# Power.net
KiCad netlist of a schematic drawn in Altium Designer
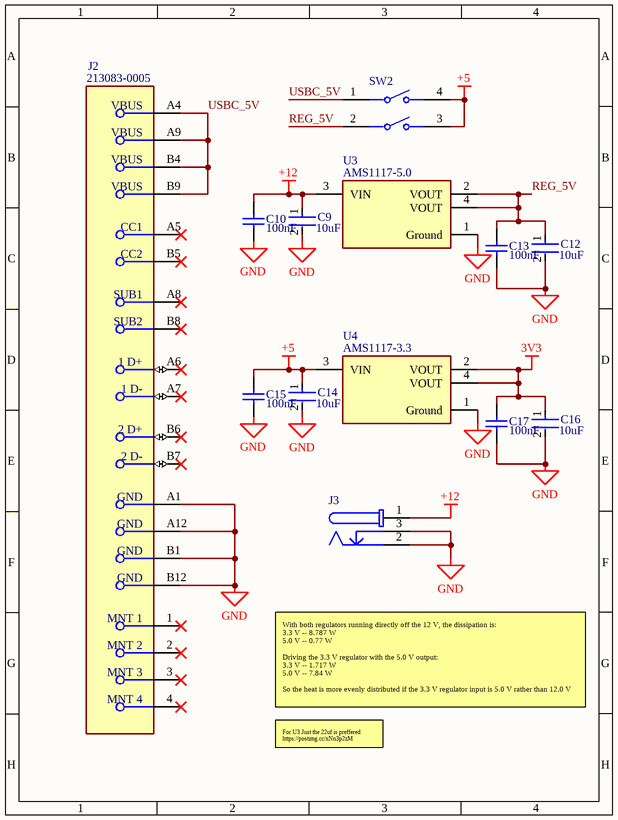
[diagram p0: Power.SchDoc]

(export (version "E")
  (design (tool "Eeschema 10.0.6"))
  (components
    (comp (ref "C9")
      (value "1206YD106KAT2A")
      (footprint "FP-1206-L_3_2_0_2-W_1_6_0-IPC_B")
      (description "General Purpose Ceramic Capacitor, 1206, 10uF, 10%, X5R, 15%, 16V")
      (fields
        (field (name "TOLERANCE") "10%")
        (field (name "CAPACITANCE") "10uF")
        (field (name "VOLTAGE") "16V")
      )
      (libsource (lib "Altium Content Vault") (part "02cd4be3c70576c341d710602a673aa"))
    )
    (comp (ref "C10")
      (value "100nF")
      (footprint "CAPC2013X140X50LL20T25")
      (fields
        (field (name "MANUFACTURER") "AVX Interconnect / Elco")
        (field (name "PART NUMBER") "08055F104KAT2A")
      )
      (libsource (lib "Altium Content Vault") (part "CAP"))
    )
    (comp (ref "C12")
      (value "1206YD106KAT2A")
      (footprint "FP-1206-L_3_2_0_2-W_1_6_0-IPC_B")
      (description "General Purpose Ceramic Capacitor, 1206, 10uF, 10%, X5R, 15%, 16V")
      (fields
        (field (name "TOLERANCE") "10%")
        (field (name "CAPACITANCE") "10uF")
        (field (name "VOLTAGE") "16V")
      )
      (libsource (lib "Altium Content Vault") (part "02cd4be3c70576c341d710602a673aa"))
    )
    (comp (ref "C13")
      (value "100nF")
      (footprint "CAPC2013X140X50LL20T25")
      (fields
        (field (name "MANUFACTURER") "AVX Interconnect / Elco")
        (field (name "PART NUMBER") "08055F104KAT2A")
      )
      (libsource (lib "Altium Content Vault") (part "CAP"))
    )
    (comp (ref "C14")
      (value "1206YD106KAT2A")
      (footprint "FP-1206-L_3_2_0_2-W_1_6_0-IPC_B")
      (description "General Purpose Ceramic Capacitor, 1206, 10uF, 10%, X5R, 15%, 16V")
      (fields
        (field (name "TOLERANCE") "10%")
        (field (name "CAPACITANCE") "10uF")
        (field (name "VOLTAGE") "16V")
      )
      (libsource (lib "Altium Content Vault") (part "02cd4be3c70576c341d710602a673aa"))
    )
    (comp (ref "C15")
      (value "100nF")
      (footprint "CAPC2013X140X50LL20T25")
      (fields
        (field (name "MANUFACTURER") "AVX Interconnect / Elco")
        (field (name "PART NUMBER") "08055F104KAT2A")
      )
      (libsource (lib "Altium Content Vault") (part "CAP"))
    )
    (comp (ref "C16")
      (value "1206YD106KAT2A")
      (footprint "FP-1206-L_3_2_0_2-W_1_6_0-IPC_B")
      (description "General Purpose Ceramic Capacitor, 1206, 10uF, 10%, X5R, 15%, 16V")
      (fields
        (field (name "TOLERANCE") "10%")
        (field (name "CAPACITANCE") "10uF")
        (field (name "VOLTAGE") "16V")
      )
      (libsource (lib "Altium Content Vault") (part "02cd4be3c70576c341d710602a673aa"))
    )
    (comp (ref "C17")
      (value "100nF")
      (footprint "CAPC2013X140X50LL20T25")
      (fields
        (field (name "MANUFACTURER") "AVX Interconnect / Elco")
        (field (name "PART NUMBER") "08055F104KAT2A")
      )
      (libsource (lib "Altium Content Vault") (part "CAP"))
    )
    (comp (ref "J2")
      (value "213083-0005")
      (footprint "FP-2130830005-MFG")
      (description "CONN RCP USB2.0 TYP C 24P SMD RA")
      (libsource (lib "Altium Content Vault") (part "19c02d2f2bfb43c17c60460c929b15b"))
    )
    (comp (ref "J3")
      (value "694106301002")
      (footprint "694106301002")
      (libsource (lib "Altium Content Vault") (part "DC Power Jack"))
    )
    (comp (ref "SW2")
      (value "A6T-2104")
      (footprint "FP-A6T-2104-MFG")
      (description "SWITCH SLIDE DIP SPST 25MA 24V")
      (libsource (lib "Altium Content Vault") (part "2136f0c9a6aaee9f8cd998ea1811686"))
    )
    (comp (ref "U3")
      (value "AMS1117-5.0")
      (footprint "FP-AMS1117-IPC_C")
      (description "LDO Voltage Regulators 1A, 3.3V")
      (fields
        (field (name "MANUFACTURER PART NUMBER") "AMS1117-3.3")
        (field (name "OCTOPART") "https://octopart.com/ams1117-3.3-advanced+monolithic+systems-25899300")
      )
      (libsource (lib "Altium Content Vault") (part "8bdbb5f8e77002000e30dd2845d0354"))
    )
    (comp (ref "U4")
      (value "AMS1117-3.3")
      (footprint "FP-AMS1117-IPC_C")
      (description "LDO Voltage Regulators 1A, 3.3V")
      (fields
        (field (name "OCTOPART") "https://octopart.com/ams1117-3.3-advanced+monolithic+systems-25899300")
        (field (name "MANUFACTURER") "Advanced Monolithic Systems")
      )
      (libsource (lib "Altium Content Vault") (part "8bdbb5f8e77002000e30dd2845d0354"))
    )
  )
  (nets
    (net (code "1") (name "+5") (class "Default")
      (node (ref "C14") (pin "1") (pinfunction "1_1") (pintype "passive"))
      (node (ref "C15") (pin "2") (pinfunction "2_2") (pintype "passive"))
      (node (ref "SW2") (pin "3") (pinfunction "3_3") (pintype "passive"))
      (node (ref "SW2") (pin "4") (pinfunction "4_4") (pintype "passive"))
      (node (ref "U4") (pin "3") (pinfunction "VIN_3") (pintype "power_in"))
    )
    (net (code "2") (name "+12") (class "Default")
      (node (ref "C10") (pin "2") (pinfunction "2_2") (pintype "passive"))
      (node (ref "C9") (pin "1") (pinfunction "1_1") (pintype "passive"))
      (node (ref "J3") (pin "1") (pinfunction "1_1") (pintype "passive"))
      (node (ref "U3") (pin "3") (pinfunction "VIN_3") (pintype "power_in"))
    )
    (net (code "3") (name "/REG_5V") (class "Default")
      (node (ref "C12") (pin "1") (pinfunction "1_1") (pintype "passive"))
      (node (ref "C13") (pin "2") (pinfunction "2_2") (pintype "passive"))
      (node (ref "SW2") (pin "2") (pinfunction "2_2") (pintype "passive"))
      (node (ref "U3") (pin "2") (pinfunction "VOUT_2") (pintype "passive"))
      (node (ref "U3") (pin "4") (pinfunction "VOUT_4") (pintype "passive"))
    )
    (net (code "4") (name "/USBC_5V") (class "Default")
      (node (ref "J2") (pin "A4") (pinfunction "VBUS_A4") (pintype "power_in"))
      (node (ref "J2") (pin "A9") (pinfunction "VBUS_A9") (pintype "power_in"))
      (node (ref "J2") (pin "B4") (pinfunction "VBUS_B4") (pintype "power_in"))
      (node (ref "J2") (pin "B9") (pinfunction "VBUS_B9") (pintype "power_in"))
      (node (ref "SW2") (pin "1") (pinfunction "1_1") (pintype "passive"))
    )
    (net (code "5") (name "3V3") (class "Default")
      (node (ref "C16") (pin "1") (pinfunction "1_1") (pintype "passive"))
      (node (ref "C17") (pin "2") (pinfunction "2_2") (pintype "passive"))
      (node (ref "U4") (pin "2") (pinfunction "VOUT_2") (pintype "passive"))
      (node (ref "U4") (pin "4") (pinfunction "VOUT_4") (pintype "passive"))
    )
    (net (code "6") (name "GND") (class "Default")
      (node (ref "C10") (pin "1") (pinfunction "1_1") (pintype "passive"))
      (node (ref "C12") (pin "2") (pinfunction "2_2") (pintype "passive"))
      (node (ref "C13") (pin "1") (pinfunction "1_1") (pintype "passive"))
      (node (ref "C14") (pin "2") (pinfunction "2_2") (pintype "passive"))
      (node (ref "C15") (pin "1") (pinfunction "1_1") (pintype "passive"))
      (node (ref "C16") (pin "2") (pinfunction "2_2") (pintype "passive"))
      (node (ref "C17") (pin "1") (pinfunction "1_1") (pintype "passive"))
      (node (ref "C9") (pin "2") (pinfunction "2_2") (pintype "passive"))
      (node (ref "J2") (pin "A1") (pinfunction "GND_A1") (pintype "power_in"))
      (node (ref "J2") (pin "A12") (pinfunction "GND_A12") (pintype "power_in"))
      (node (ref "J2") (pin "B1") (pinfunction "GND_B1") (pintype "power_in"))
      (node (ref "J2") (pin "B12") (pinfunction "GND_B12") (pintype "power_in"))
      (node (ref "J3") (pin "2") (pinfunction "2_2") (pintype "passive"))
      (node (ref "J3") (pin "3") (pinfunction "3_3") (pintype "passive"))
      (node (ref "U3") (pin "1") (pinfunction "Ground_1") (pintype "power_in"))
      (node (ref "U4") (pin "1") (pinfunction "Ground_1") (pintype "power_in"))
    )
    (net (code "7") (name "unconnected-(J2-1_D+-PadA6)") (class "Default")
      (node (ref "J2") (pin "A6") (pinfunction "1_D+_A6") (pintype "bidirectional+no_connect"))
    )
    (net (code "8") (name "unconnected-(J2-1_D--PadA7)") (class "Default")
      (node (ref "J2") (pin "A7") (pinfunction "1_D-_A7") (pintype "bidirectional+no_connect"))
    )
    (net (code "9") (name "unconnected-(J2-2_D+-PadB6)") (class "Default")
      (node (ref "J2") (pin "B6") (pinfunction "2_D+_B6") (pintype "bidirectional+no_connect"))
    )
    (net (code "10") (name "unconnected-(J2-2_D--PadB7)") (class "Default")
      (node (ref "J2") (pin "B7") (pinfunction "2_D-_B7") (pintype "bidirectional+no_connect"))
    )
    (net (code "11") (name "unconnected-(J2-CC1-PadA5)") (class "Default")
      (node (ref "J2") (pin "A5") (pinfunction "CC1_A5") (pintype "passive+no_connect"))
    )
    (net (code "12") (name "unconnected-(J2-CC2-PadB5)") (class "Default")
      (node (ref "J2") (pin "B5") (pinfunction "CC2_B5") (pintype "passive+no_connect"))
    )
    (net (code "13") (name "unconnected-(J2-MNT_1-Pad1)") (class "Default")
      (node (ref "J2") (pin "1") (pinfunction "MNT_1_1") (pintype "passive+no_connect"))
    )
    (net (code "14") (name "unconnected-(J2-MNT_2-Pad2)") (class "Default")
      (node (ref "J2") (pin "2") (pinfunction "MNT_2_2") (pintype "passive+no_connect"))
    )
    (net (code "15") (name "unconnected-(J2-MNT_3-Pad3)") (class "Default")
      (node (ref "J2") (pin "3") (pinfunction "MNT_3_3") (pintype "passive+no_connect"))
    )
    (net (code "16") (name "unconnected-(J2-MNT_4-Pad4)") (class "Default")
      (node (ref "J2") (pin "4") (pinfunction "MNT_4_4") (pintype "passive+no_connect"))
    )
    (net (code "17") (name "unconnected-(J2-SUB1-PadA8)") (class "Default")
      (node (ref "J2") (pin "A8") (pinfunction "SUB1_A8") (pintype "passive+no_connect"))
    )
    (net (code "18") (name "unconnected-(J2-SUB2-PadB8)") (class "Default")
      (node (ref "J2") (pin "B8") (pinfunction "SUB2_B8") (pintype "passive+no_connect"))
    )
  )
)
